# Light_Control_Compact.net
KiCad netlist of a schematic drawn in Altium Designer
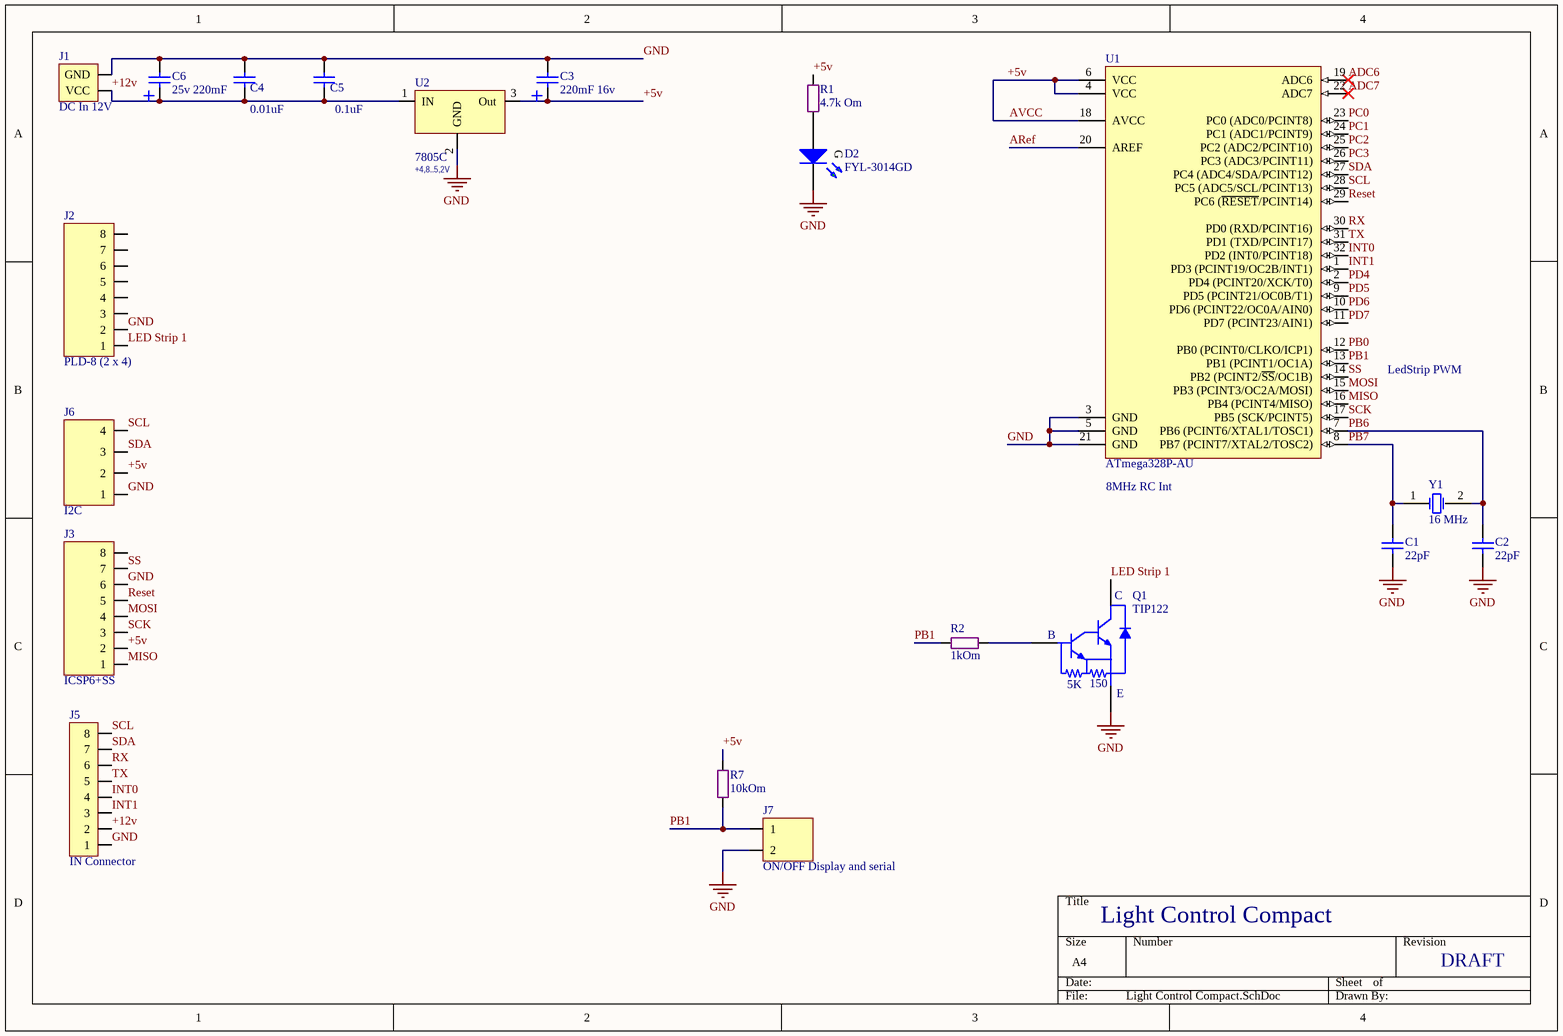
[diagram p0: Light Control Compact.SchDoc]

(export (version "E")
  (design (tool "Eeschema 10.0.6"))
  (components
    (comp (ref "C1")
      (value "22pF")
      (footprint "Capacitor:SMD 0805 (2012)")
      (description "Capacitor")
      (libsource (lib "Capacitor") (part "Cap SMD 0402-1812"))
    )
    (comp (ref "C2")
      (value "22pF")
      (footprint "Capacitor:SMD 0805 (2012)")
      (description "Capacitor")
      (libsource (lib "Capacitor") (part "Cap SMD 0402-1812"))
    )
    (comp (ref "C3")
      (value "220mF 16v")
      (footprint "Capacitor:Cap E p2mm D6.5xH11")
      (description "Capacitor")
      (libsource (lib "Capacitor") (part "Cap E 220mF x 16V"))
    )
    (comp (ref "C4")
      (value "0.01uF")
      (footprint "Capacitor:SMD 0805 (2012)")
      (description "Capacitor")
      (libsource (lib "Capacitor") (part "Cap SMD 0402-1812"))
    )
    (comp (ref "C5")
      (value "0.1uF")
      (footprint "Capacitor:SMD 0805 (2012)")
      (description "Capacitor")
      (libsource (lib "Capacitor") (part "Cap SMD 0402-1812"))
    )
    (comp (ref "C6")
      (value "25v 220mF")
      (footprint "Capacitor:Cap E p2mm D6.5xH11")
      (description "Capacitor")
      (libsource (lib "Capacitor") (part "Cap E 220mF x 16V"))
    )
    (comp (ref "D2")
      (value "FYL-3014GD")
      (footprint "LED:LED Round 3mm Green")
      (description "2.1v 10mA, 15-30mCd")
      (libsource (lib "LED") (part "Led Round 3mm Green"))
    )
    (comp (ref "J1")
      (value "DC In 12V")
      (footprint "Connector:DC Connector")
      (description "DC Connector")
      (libsource (lib "Connector") (part "DC Connector (PJ-002B)"))
    )
    (comp (ref "J2")
      (value "PLD-8 (2 x 4)")
      (footprint "Connector:Line 2.54 X 8D (2 x 4)")
      (description "Vert, Sgl line, Male")
      (libsource (lib "Connector") (part "PLD-8 (2 x 4)"))
    )
    (comp (ref "J3")
      (value "ICSP6+SS")
      (footprint "Connector:Line 2.54 X 8D (2 x 4)")
      (description "Vert, Sgl line, Male")
      (libsource (lib "Connector") (part "PLD-8 (2 x 4)"))
    )
    (comp (ref "J5")
      (value "IN Connector")
      (footprint "Connector:Molex Micro-Fit 3.0 - 8 pin D R")
      (description "Horisontal, Dbl line, Male - 3mm")
      (libsource (lib "Connector") (part "Micro-Fit 8R (2x4)"))
    )
    (comp (ref "J6")
      (value "I2C")
      (footprint "Connector:Line 2.54 X 4")
      (description "Vert, Sgl line, Male")
      (libsource (lib "Connector") (part "PLS-4"))
    )
    (comp (ref "J7")
      (value "ON/OFF Display and serial")
      (footprint "Connector:Line 2.54 x 2")
      (description "Vert, Sgl line, Male")
      (libsource (lib "Connector") (part "PLS-2"))
    )
    (comp (ref "Q1")
      (value "TIP122")
      (footprint "GeneralCases:TO220-2")
      (description "NPN Darlington 5A, 65W, 100V, h>1000")
      (libsource (lib "Transistor") (part "TIP122"))
    )
    (comp (ref "R1")
      (value "4.7k Om")
      (footprint "PassiveComponents:SMD 0805 (2012)")
      (libsource (lib "PassiveComponents") (part "Res All Types"))
    )
    (comp (ref "R2")
      (value "1kOm")
      (footprint "PassiveComponents:SMD 0805 (2012)")
      (libsource (lib "PassiveComponents") (part "Res All Types"))
    )
    (comp (ref "R7")
      (value "10kOm")
      (footprint "PassiveComponents:SMD 0805 (2012)")
      (libsource (lib "PassiveComponents") (part "Res All Types"))
    )
    (comp (ref "U1")
      (value "ATmega328P-AU")
      (footprint "32A_N")
      (fields (field (name "PUBLISHER") "Altium Limited"))
      (libsource (lib "Atmel Microcontroller 8-Bit megaAVR") (part "ATmega328P-AU"))
    )
    (comp (ref "U2")
      (value "7805C")
      (footprint "GeneralCases:D-PAK")
      (description "Voltage Regulator")
      (fields (field (name "MANUFACTURER") "Интеграл") (field (name "V OUT") "+4,8..5,2V"))
      (libsource (lib "PowerAdjusment") (part "7805C"))
    )
    (comp (ref "Y1")
      (value "16 MHz")
      (footprint "PassiveComponents:XTAL - 2")
      (description "Crystal Oscillator")
      (fields (field (name "PUBLISHER") "Altium Limited"))
      (libsource (lib "PassiveComponents") (part "XTAL"))
    )
  )
  (nets
    (net (code "1") (name "/+5v") (class "Default")
      (node (ref "C3") (pin "1") (pinfunction "1_1") (pintype "passive"))
      (node (ref "J3") (pin "2") (pinfunction "2_2") (pintype "passive"))
      (node (ref "J6") (pin "2") (pinfunction "2_2") (pintype "passive"))
      (node (ref "R1") (pin "1") (pinfunction "1_1") (pintype "passive"))
      (node (ref "R7") (pin "2") (pinfunction "2_2") (pintype "passive"))
      (node (ref "U1") (pin "18") (pinfunction "AVCC_18") (pintype "power_in"))
      (node (ref "U1") (pin "4") (pinfunction "VCC_4") (pintype "power_in"))
      (node (ref "U1") (pin "6") (pinfunction "VCC_6") (pintype "power_in"))
      (node (ref "U2") (pin "3") (pinfunction "Out_3") (pintype "power_in"))
    )
    (net (code "2") (name "/+12v") (class "Default")
      (node (ref "C4") (pin "2") (pinfunction "2_2") (pintype "passive"))
      (node (ref "C5") (pin "2") (pinfunction "2_2") (pintype "passive"))
      (node (ref "C6") (pin "1") (pinfunction "1_1") (pintype "passive"))
      (node (ref "J1") (pin "VCC") (pinfunction "VCC_VCC") (pintype "passive"))
      (node (ref "J5") (pin "2") (pinfunction "2_2") (pintype "passive"))
      (node (ref "U2") (pin "1") (pinfunction "IN_1") (pintype "power_in"))
    )
    (net (code "3") (name "/ADC6") (class "Default")
      (node (ref "U1") (pin "19") (pinfunction "ADC6_19") (pintype "input+no_connect"))
    )
    (net (code "4") (name "/ADC7") (class "Default")
      (node (ref "U1") (pin "22") (pinfunction "ADC7_22") (pintype "input+no_connect"))
    )
    (net (code "5") (name "/ARef") (class "Default")
      (node (ref "U1") (pin "20") (pinfunction "AREF_20") (pintype "passive"))
    )
    (net (code "6") (name "/INT0") (class "Default")
      (node (ref "J5") (pin "4") (pinfunction "4_4") (pintype "passive"))
      (node (ref "U1") (pin "32") (pinfunction "PD2_(INT0/PCINT18)_32") (pintype "bidirectional"))
    )
    (net (code "7") (name "/INT1") (class "Default")
      (node (ref "J5") (pin "3") (pinfunction "3_3") (pintype "passive"))
      (node (ref "U1") (pin "1") (pinfunction "PD3_(PCINT19/OC2B/INT1)_1") (pintype "bidirectional"))
    )
    (net (code "8") (name "/LED Strip 1") (class "Default")
      (node (ref "J2") (pin "1") (pinfunction "1_1") (pintype "passive"))
      (node (ref "Q1") (pin "2") (pinfunction "C_2") (pintype "passive"))
    )
    (net (code "9") (name "/MISO") (class "Default")
      (node (ref "J3") (pin "1") (pinfunction "1_1") (pintype "passive"))
      (node (ref "U1") (pin "16") (pinfunction "PB4_(PCINT4/MISO)_16") (pintype "bidirectional"))
    )
    (net (code "10") (name "/MOSI") (class "Default")
      (node (ref "J3") (pin "4") (pinfunction "4_4") (pintype "passive"))
      (node (ref "U1") (pin "15") (pinfunction "PB3_(PCINT3/OC2A/MOSI)_15") (pintype "bidirectional"))
    )
    (net (code "11") (name "/PB0") (class "Default")
      (node (ref "U1") (pin "12") (pinfunction "PB0_(PCINT0/CLKO/ICP1)_12") (pintype "bidirectional"))
    )
    (net (code "12") (name "/PB1") (class "Default")
      (node (ref "J7") (pin "1") (pinfunction "1_1") (pintype "passive"))
      (node (ref "R2") (pin "1") (pinfunction "1_1") (pintype "passive"))
      (node (ref "R7") (pin "1") (pinfunction "1_1") (pintype "passive"))
      (node (ref "U1") (pin "13") (pinfunction "PB1_(PCINT1/OC1A)_13") (pintype "bidirectional"))
    )
    (net (code "13") (name "/PB6") (class "Default")
      (node (ref "C2") (pin "2") (pinfunction "2_2") (pintype "passive"))
      (node (ref "U1") (pin "7") (pinfunction "PB6_(PCINT6/XTAL1/TOSC1)_7") (pintype "bidirectional"))
      (node (ref "Y1") (pin "2") (pinfunction "OSC2_2") (pintype "passive"))
    )
    (net (code "14") (name "/PB7") (class "Default")
      (node (ref "C1") (pin "2") (pinfunction "2_2") (pintype "passive"))
      (node (ref "U1") (pin "8") (pinfunction "PB7_(PCINT7/XTAL2/TOSC2)_8") (pintype "bidirectional"))
      (node (ref "Y1") (pin "1") (pinfunction "OSC1_1") (pintype "passive"))
    )
    (net (code "15") (name "/PC0") (class "Default")
      (node (ref "U1") (pin "23") (pinfunction "PC0_(ADC0/PCINT8)_23") (pintype "bidirectional"))
    )
    (net (code "16") (name "/PC1") (class "Default")
      (node (ref "U1") (pin "24") (pinfunction "PC1_(ADC1/PCINT9)_24") (pintype "bidirectional"))
    )
    (net (code "17") (name "/PC2") (class "Default")
      (node (ref "U1") (pin "25") (pinfunction "PC2_(ADC2/PCINT10)_25") (pintype "bidirectional"))
    )
    (net (code "18") (name "/PC3") (class "Default")
      (node (ref "U1") (pin "26") (pinfunction "PC3_(ADC3/PCINT11)_26") (pintype "bidirectional"))
    )
    (net (code "19") (name "/PD4") (class "Default")
      (node (ref "U1") (pin "2") (pinfunction "PD4_(PCINT20/XCK/T0)_2") (pintype "bidirectional"))
    )
    (net (code "20") (name "/PD5") (class "Default")
      (node (ref "U1") (pin "9") (pinfunction "PD5_(PCINT21/OC0B/T1)_9") (pintype "bidirectional"))
    )
    (net (code "21") (name "/PD6") (class "Default")
      (node (ref "U1") (pin "10") (pinfunction "PD6_(PCINT22/OC0A/AIN0)_10") (pintype "bidirectional"))
    )
    (net (code "22") (name "/PD7") (class "Default")
      (node (ref "U1") (pin "11") (pinfunction "PD7_(PCINT23/AIN1)_11") (pintype "bidirectional"))
    )
    (net (code "23") (name "/RX") (class "Default")
      (node (ref "J5") (pin "6") (pinfunction "6_6") (pintype "passive"))
      (node (ref "U1") (pin "30") (pinfunction "PD0_(RXD/PCINT16)_30") (pintype "bidirectional"))
    )
    (net (code "24") (name "/Reset") (class "Default")
      (node (ref "J3") (pin "5") (pinfunction "5_5") (pintype "passive"))
      (node (ref "U1") (pin "29") (pinfunction "PC6_(~{RESET}/PCINT14)_29") (pintype "bidirectional"))
    )
    (net (code "25") (name "/SCK") (class "Default")
      (node (ref "J3") (pin "3") (pinfunction "3_3") (pintype "passive"))
      (node (ref "U1") (pin "17") (pinfunction "PB5_(SCK/PCINT5)_17") (pintype "bidirectional"))
    )
    (net (code "26") (name "/SCL") (class "Default")
      (node (ref "J5") (pin "8") (pinfunction "8_8") (pintype "passive"))
      (node (ref "J6") (pin "4") (pinfunction "4_4") (pintype "passive"))
      (node (ref "U1") (pin "28") (pinfunction "PC5_(ADC5/SCL/PCINT13)_28") (pintype "bidirectional"))
    )
    (net (code "27") (name "/SDA") (class "Default")
      (node (ref "J5") (pin "7") (pinfunction "7_7") (pintype "passive"))
      (node (ref "J6") (pin "3") (pinfunction "3_3") (pintype "passive"))
      (node (ref "U1") (pin "27") (pinfunction "PC4_(ADC4/SDA/PCINT12)_27") (pintype "bidirectional"))
    )
    (net (code "28") (name "/SS") (class "Default")
      (node (ref "J3") (pin "7") (pinfunction "7_7") (pintype "passive"))
      (node (ref "U1") (pin "14") (pinfunction "PB2_(PCINT2/~{SS}/OC1B)_14") (pintype "bidirectional"))
    )
    (net (code "29") (name "/TX") (class "Default")
      (node (ref "J5") (pin "5") (pinfunction "5_5") (pintype "passive"))
      (node (ref "U1") (pin "31") (pinfunction "PD1_(TXD/PCINT17)_31") (pintype "bidirectional"))
    )
    (net (code "30") (name "GND") (class "Default")
      (node (ref "C1") (pin "1") (pinfunction "1_1") (pintype "passive"))
      (node (ref "C2") (pin "1") (pinfunction "1_1") (pintype "passive"))
      (node (ref "C3") (pin "2") (pinfunction "2_2") (pintype "passive"))
      (node (ref "C4") (pin "1") (pinfunction "1_1") (pintype "passive"))
      (node (ref "C5") (pin "1") (pinfunction "1_1") (pintype "passive"))
      (node (ref "C6") (pin "2") (pinfunction "2_2") (pintype "passive"))
      (node (ref "D2") (pin "K") (pinfunction "K_K") (pintype "passive"))
      (node (ref "J1") (pin "GND") (pinfunction "GND_GND") (pintype "passive"))
      (node (ref "J2") (pin "2") (pinfunction "2_2") (pintype "passive"))
      (node (ref "J3") (pin "6") (pinfunction "6_6") (pintype "passive"))
      (node (ref "J5") (pin "1") (pinfunction "1_1") (pintype "passive"))
      (node (ref "J6") (pin "1") (pinfunction "1_1") (pintype "passive"))
      (node (ref "J7") (pin "2") (pinfunction "2_2") (pintype "passive"))
      (node (ref "Q1") (pin "3") (pinfunction "E_3") (pintype "passive"))
      (node (ref "U1") (pin "21") (pinfunction "GND_21") (pintype "power_in"))
      (node (ref "U1") (pin "3") (pinfunction "GND_3") (pintype "power_in"))
      (node (ref "U1") (pin "5") (pinfunction "GND_5") (pintype "power_in"))
      (node (ref "U2") (pin "2") (pinfunction "GND_2") (pintype "passive"))
    )
    (net (code "31") (name "Net-(D2-PadA)") (class "Default")
      (node (ref "D2") (pin "A") (pinfunction "A_A") (pintype "passive"))
      (node (ref "R1") (pin "2") (pinfunction "2_2") (pintype "passive"))
    )
    (net (code "32") (name "Net-(Q1-B)") (class "Default")
      (node (ref "Q1") (pin "1") (pinfunction "B_1") (pintype "passive"))
      (node (ref "R2") (pin "2") (pinfunction "2_2") (pintype "passive"))
    )
    (net (code "33") (name "unconnected-(J2-Pad3)") (class "Default")
      (node (ref "J2") (pin "3") (pinfunction "3_3") (pintype "passive"))
    )
    (net (code "34") (name "unconnected-(J2-Pad4)") (class "Default")
      (node (ref "J2") (pin "4") (pinfunction "4_4") (pintype "passive"))
    )
    (net (code "35") (name "unconnected-(J2-Pad5)") (class "Default")
      (node (ref "J2") (pin "5") (pinfunction "5_5") (pintype "passive"))
    )
    (net (code "36") (name "unconnected-(J2-Pad6)") (class "Default")
      (node (ref "J2") (pin "6") (pinfunction "6_6") (pintype "passive"))
    )
    (net (code "37") (name "unconnected-(J2-Pad7)") (class "Default")
      (node (ref "J2") (pin "7") (pinfunction "7_7") (pintype "passive"))
    )
    (net (code "38") (name "unconnected-(J2-Pad8)") (class "Default")
      (node (ref "J2") (pin "8") (pinfunction "8_8") (pintype "passive"))
    )
    (net (code "39") (name "unconnected-(J3-Pad8)") (class "Default")
      (node (ref "J3") (pin "8") (pinfunction "8_8") (pintype "passive"))
    )
  )
)
